# STlink.net
KiCad netlist of a schematic drawn in Altium Designer
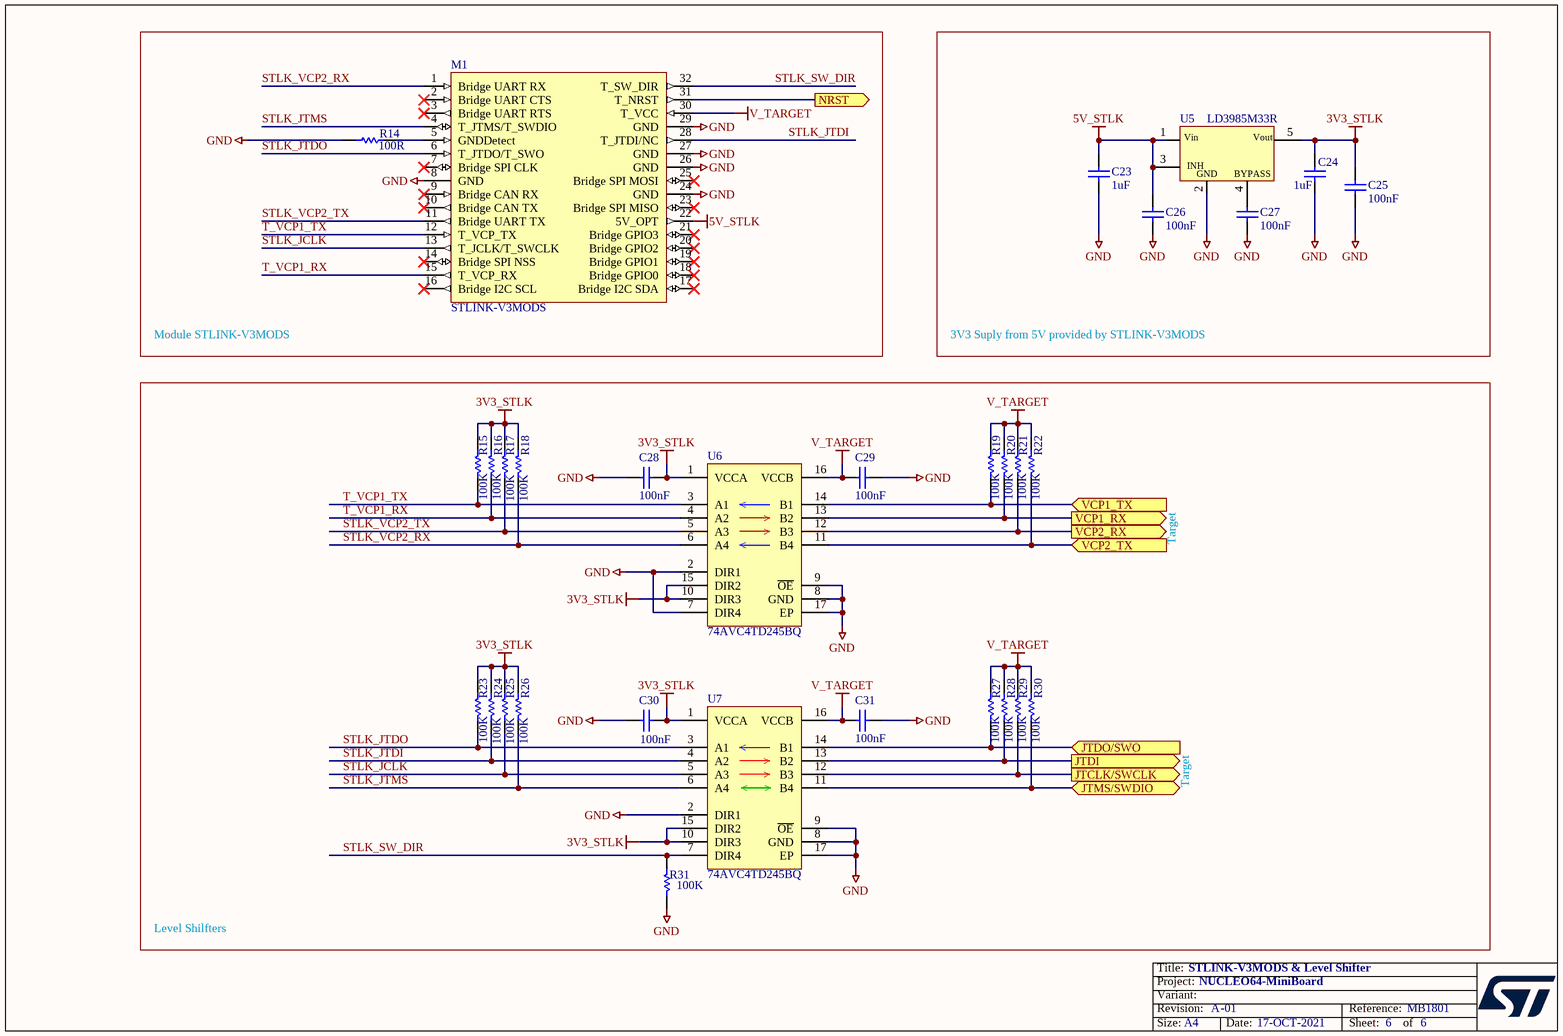
[diagram p0: STlink.SchDoc]

(export (version "E")
  (design (tool "Eeschema 10.0.6"))
  (components
    (comp (ref "C23")
      (value "1uF")
      (footprint "C0402")
      (description "Capacitor, MLCC, 1uF, 10V, X5R, +/-10%, 0402, T=0.5mm")
      (fields
        (field (name "INTERNAL_PART_NUMBER") "MCD-01722")
        (field (name "MANUFACTURER_PART_NUMBER") "CC0402KRX5R6BB105")
      )
      (libsource (lib "MCD_PARTS_database") (part "Capacitor"))
    )
    (comp (ref "C24")
      (value "1uF")
      (footprint "C0402")
      (description "Capacitor, MLCC, 1uF, 10V, X5R, +/-10%, 0402, T=0.5mm")
      (fields
        (field (name "INTERNAL_PART_NUMBER") "MCD-01722")
        (field (name "MANUFACTURER_PART_NUMBER") "CC0402KRX5R6BB105")
      )
      (libsource (lib "MCD_PARTS_database") (part "Capacitor"))
    )
    (comp (ref "C25")
      (value "100nF")
      (footprint "C0402")
      (description "Capacitor, MLCC, 100nF, 25V, X7R, +/-10%, 0402, T=0.5mm")
      (fields (field (name "INTERNAL_PART_NUMBER") "MCD-02355") (field (name "MANUFACTURER") "WALSIN"))
      (libsource (lib "MCD_PARTS_database") (part "Capacitor"))
    )
    (comp (ref "C26")
      (value "100nF")
      (footprint "C0402")
      (description "Capacitor, MLCC, 100nF, 25V, X7R, +/-10%, 0402, T=0.5mm")
      (fields (field (name "INTERNAL_PART_NUMBER") "MCD-02355") (field (name "MANUFACTURER") "WALSIN"))
      (libsource (lib "MCD_PARTS_database") (part "Capacitor"))
    )
    (comp (ref "C27")
      (value "100nF")
      (footprint "C0402")
      (description "Capacitor, MLCC, 100nF, 25V, X7R, +/-10%, 0402, T=0.5mm")
      (fields (field (name "INTERNAL_PART_NUMBER") "MCD-02355") (field (name "MANUFACTURER") "WALSIN"))
      (libsource (lib "MCD_PARTS_database") (part "Capacitor"))
    )
    (comp (ref "C28")
      (value "100nF")
      (footprint "C0402")
      (description "Capacitor, MLCC, 100nF, 25V, X7R, +/-10%, 0402, T=0.5mm")
      (fields (field (name "INTERNAL_PART_NUMBER") "MCD-02355") (field (name "MANUFACTURER") "WALSIN"))
      (libsource (lib "MCD_PARTS_database") (part "Capacitor"))
    )
    (comp (ref "C29")
      (value "100nF")
      (footprint "C0402")
      (description "Capacitor, MLCC, 100nF, 25V, X7R, +/-10%, 0402, T=0.5mm")
      (fields (field (name "INTERNAL_PART_NUMBER") "MCD-02355") (field (name "MANUFACTURER") "WALSIN"))
      (libsource (lib "MCD_PARTS_database") (part "Capacitor"))
    )
    (comp (ref "C30")
      (value "100nF")
      (footprint "C0402")
      (description "Capacitor, MLCC, 100nF, 25V, X7R, +/-10%, 0402, T=0.5mm")
      (fields (field (name "INTERNAL_PART_NUMBER") "MCD-02355") (field (name "MANUFACTURER") "WALSIN"))
      (libsource (lib "MCD_PARTS_database") (part "Capacitor"))
    )
    (comp (ref "C31")
      (value "100nF")
      (footprint "C0402")
      (description "Capacitor, MLCC, 100nF, 25V, X7R, +/-10%, 0402, T=0.5mm")
      (fields (field (name "INTERNAL_PART_NUMBER") "MCD-02355") (field (name "MANUFACTURER") "WALSIN"))
      (libsource (lib "MCD_PARTS_database") (part "Capacitor"))
    )
    (comp (ref "M1")
      (value "STLINK-V3MODS")
      (footprint "MOD_STLINK-V3M_MB1467")
      (description "STLINK-V3MODS module")
      (fields
        (field (name "INTERNAL_PART_NUMBER") "MCD-01983")
        (field (name "MANUFACTURER") "STMICROELECTRONICS")
      )
      (libsource (lib "MCD_PARTS_database") (part "STLINK-V3MODS"))
    )
    (comp (ref "R14")
      (value "100R")
      (footprint "R0402")
      (description "Resistor, 100R, 0402, +/-1%, 1/16W")
      (fields (field (name "INTERNAL_PART_NUMBER") "MCD-00119") (field (name "MANUFACTURER") "YAGEO"))
      (libsource (lib "MCD_PARTS_database") (part "Resistor"))
    )
    (comp (ref "R15")
      (value "100K")
      (footprint "R0402")
      (description "Resistor, 100K, 0402, +/-1%, 1/16W")
      (fields
        (field (name "INTERNAL_PART_NUMBER") "MCD-00059")
        (field (name "MANUFACTURER_PART_NUMBER") "RC0402FR-07100KL")
      )
      (libsource (lib "MCD_PARTS_database") (part "Resistor"))
    )
    (comp (ref "R16")
      (value "100K")
      (footprint "R0402")
      (description "Resistor, 100K, 0402, +/-1%, 1/16W")
      (fields
        (field (name "INTERNAL_PART_NUMBER") "MCD-00059")
        (field (name "MANUFACTURER_PART_NUMBER") "RC0402FR-07100KL")
      )
      (libsource (lib "MCD_PARTS_database") (part "Resistor"))
    )
    (comp (ref "R17")
      (value "100K")
      (footprint "R0402")
      (description "Resistor, 100K, 0402, +/-1%, 1/16W")
      (fields
        (field (name "INTERNAL_PART_NUMBER") "MCD-00059")
        (field (name "MANUFACTURER_PART_NUMBER") "RC0402FR-07100KL")
      )
      (libsource (lib "MCD_PARTS_database") (part "Resistor"))
    )
    (comp (ref "R18")
      (value "100K")
      (footprint "R0402")
      (description "Resistor, 100K, 0402, +/-1%, 1/16W")
      (fields
        (field (name "INTERNAL_PART_NUMBER") "MCD-00059")
        (field (name "MANUFACTURER_PART_NUMBER") "RC0402FR-07100KL")
      )
      (libsource (lib "MCD_PARTS_database") (part "Resistor"))
    )
    (comp (ref "R19")
      (value "100K")
      (footprint "R0402")
      (description "Resistor, 100K, 0402, +/-1%, 1/16W")
      (fields
        (field (name "INTERNAL_PART_NUMBER") "MCD-00059")
        (field (name "MANUFACTURER_PART_NUMBER") "RC0402FR-07100KL")
      )
      (libsource (lib "MCD_PARTS_database") (part "Resistor"))
    )
    (comp (ref "R20")
      (value "100K")
      (footprint "R0402")
      (description "Resistor, 100K, 0402, +/-1%, 1/16W")
      (fields
        (field (name "INTERNAL_PART_NUMBER") "MCD-00059")
        (field (name "MANUFACTURER_PART_NUMBER") "RC0402FR-07100KL")
      )
      (libsource (lib "MCD_PARTS_database") (part "Resistor"))
    )
    (comp (ref "R21")
      (value "100K")
      (footprint "R0402")
      (description "Resistor, 100K, 0402, +/-1%, 1/16W")
      (fields
        (field (name "INTERNAL_PART_NUMBER") "MCD-00059")
        (field (name "MANUFACTURER_PART_NUMBER") "RC0402FR-07100KL")
      )
      (libsource (lib "MCD_PARTS_database") (part "Resistor"))
    )
    (comp (ref "R22")
      (value "100K")
      (footprint "R0402")
      (description "Resistor, 100K, 0402, +/-1%, 1/16W")
      (fields
        (field (name "INTERNAL_PART_NUMBER") "MCD-00059")
        (field (name "MANUFACTURER_PART_NUMBER") "RC0402FR-07100KL")
      )
      (libsource (lib "MCD_PARTS_database") (part "Resistor"))
    )
    (comp (ref "R23")
      (value "100K")
      (footprint "R0402")
      (description "Resistor, 100K, 0402, +/-1%, 1/16W")
      (fields
        (field (name "INTERNAL_PART_NUMBER") "MCD-00059")
        (field (name "MANUFACTURER_PART_NUMBER") "RC0402FR-07100KL")
      )
      (libsource (lib "MCD_PARTS_database") (part "Resistor"))
    )
    (comp (ref "R24")
      (value "100K")
      (footprint "R0402")
      (description "Resistor, 100K, 0402, +/-1%, 1/16W")
      (fields
        (field (name "INTERNAL_PART_NUMBER") "MCD-00059")
        (field (name "MANUFACTURER_PART_NUMBER") "RC0402FR-07100KL")
      )
      (libsource (lib "MCD_PARTS_database") (part "Resistor"))
    )
    (comp (ref "R25")
      (value "100K")
      (footprint "R0402")
      (description "Resistor, 100K, 0402, +/-1%, 1/16W")
      (fields
        (field (name "INTERNAL_PART_NUMBER") "MCD-00059")
        (field (name "MANUFACTURER_PART_NUMBER") "RC0402FR-07100KL")
      )
      (libsource (lib "MCD_PARTS_database") (part "Resistor"))
    )
    (comp (ref "R26")
      (value "100K")
      (footprint "R0402")
      (description "Resistor, 100K, 0402, +/-1%, 1/16W")
      (fields
        (field (name "INTERNAL_PART_NUMBER") "MCD-00059")
        (field (name "MANUFACTURER_PART_NUMBER") "RC0402FR-07100KL")
      )
      (libsource (lib "MCD_PARTS_database") (part "Resistor"))
    )
    (comp (ref "R27")
      (value "100K")
      (footprint "R0402")
      (description "Resistor, 100K, 0402, +/-1%, 1/16W")
      (fields
        (field (name "INTERNAL_PART_NUMBER") "MCD-00059")
        (field (name "MANUFACTURER_PART_NUMBER") "RC0402FR-07100KL")
      )
      (libsource (lib "MCD_PARTS_database") (part "Resistor"))
    )
    (comp (ref "R28")
      (value "100K")
      (footprint "R0402")
      (description "Resistor, 100K, 0402, +/-1%, 1/16W")
      (fields
        (field (name "INTERNAL_PART_NUMBER") "MCD-00059")
        (field (name "MANUFACTURER_PART_NUMBER") "RC0402FR-07100KL")
      )
      (libsource (lib "MCD_PARTS_database") (part "Resistor"))
    )
    (comp (ref "R29")
      (value "100K")
      (footprint "R0402")
      (description "Resistor, 100K, 0402, +/-1%, 1/16W")
      (fields
        (field (name "INTERNAL_PART_NUMBER") "MCD-00059")
        (field (name "MANUFACTURER_PART_NUMBER") "RC0402FR-07100KL")
      )
      (libsource (lib "MCD_PARTS_database") (part "Resistor"))
    )
    (comp (ref "R30")
      (value "100K")
      (footprint "R0402")
      (description "Resistor, 100K, 0402, +/-1%, 1/16W")
      (fields
        (field (name "INTERNAL_PART_NUMBER") "MCD-00059")
        (field (name "MANUFACTURER_PART_NUMBER") "RC0402FR-07100KL")
      )
      (libsource (lib "MCD_PARTS_database") (part "Resistor"))
    )
    (comp (ref "R31")
      (value "100K")
      (footprint "R0402")
      (description "Resistor, 100K, 0402, +/-1%, 1/16W")
      (fields
        (field (name "INTERNAL_PART_NUMBER") "MCD-00059")
        (field (name "MANUFACTURER_PART_NUMBER") "RC0402FR-07100KL")
      )
      (libsource (lib "MCD_PARTS_database") (part "Resistor"))
    )
    (comp (ref "U5")
      (value "LD3985M33R")
      (footprint "REG_SOT23-5L")
      (description "Ultra low drop-low noise BiCMOS voltage, regulators low ESR capacitors compatible")
      (fields
        (field (name "INTERNAL_PART_NUMBER") "MCD-00086")
        (field (name "MANUFACTURER") "STMICROELECTRONICS")
      )
      (libsource (lib "MCD_PARTS_database") (part "LD3985M33R"))
    )
    (comp (ref "U6")
      (value "74AVC4TD245BQ")
      (footprint "ICC_DHVQFN16-EPAD_SOT763-1_2P5X3P5_H0P85_P050")
      (description "4-bit dual supply translating transceiver with configurable voltage translation; 3-state")
      (fields
        (field (name "INTERNAL_PART_NUMBER") "MCD-01945")
        (field (name "MANUFACTURER_PART_NUMBER") "74AVC4TD245BQ,115")
      )
      (libsource (lib "MCD_PARTS_database") (part "74AVC4TD245BQ"))
    )
    (comp (ref "U7")
      (value "74AVC4TD245BQ")
      (footprint "ICC_DHVQFN16-EPAD_SOT763-1_2P5X3P5_H0P85_P050")
      (description "4-bit dual supply translating transceiver with configurable voltage translation; 3-state")
      (fields
        (field (name "INTERNAL_PART_NUMBER") "MCD-01945")
        (field (name "MANUFACTURER_PART_NUMBER") "74AVC4TD245BQ,115")
      )
      (libsource (lib "MCD_PARTS_database") (part "74AVC4TD245BQ"))
    )
  )
  (nets
    (net (code "1") (name "/JTCLK{slash}SWCLK") (class "Default")
      (node (ref "R29") (pin "1") (pinfunction "1_1") (pintype "passive"))
      (node (ref "U7") (pin "12") (pinfunction "B3_12") (pintype "passive"))
    )
    (net (code "2") (name "/JTDI") (class "Default")
      (node (ref "R28") (pin "1") (pinfunction "1_1") (pintype "passive"))
      (node (ref "U7") (pin "13") (pinfunction "B2_13") (pintype "passive"))
    )
    (net (code "3") (name "/JTDO{slash}SWO") (class "Default")
      (node (ref "R27") (pin "1") (pinfunction "1_1") (pintype "passive"))
      (node (ref "U7") (pin "14") (pinfunction "B1_14") (pintype "passive"))
    )
    (net (code "4") (name "/JTMS{slash}SWDIO") (class "Default")
      (node (ref "R30") (pin "1") (pinfunction "1_1") (pintype "passive"))
      (node (ref "U7") (pin "11") (pinfunction "B4_11") (pintype "passive"))
    )
    (net (code "5") (name "/NRST") (class "Default")
      (node (ref "M1") (pin "31") (pinfunction "T_NRST_31") (pintype "output"))
    )
    (net (code "6") (name "/STLK_JCLK") (class "Default")
      (node (ref "M1") (pin "13") (pinfunction "T_JCLK/T_SWCLK_13") (pintype "output"))
      (node (ref "R25") (pin "1") (pinfunction "1_1") (pintype "passive"))
      (node (ref "U7") (pin "5") (pinfunction "A3_5") (pintype "passive"))
    )
    (net (code "7") (name "/STLK_JTDI") (class "Default")
      (node (ref "M1") (pin "28") (pinfunction "T_JTDI/NC_28") (pintype "output"))
      (node (ref "R24") (pin "1") (pinfunction "1_1") (pintype "passive"))
      (node (ref "U7") (pin "4") (pinfunction "A2_4") (pintype "passive"))
    )
    (net (code "8") (name "/STLK_JTDO") (class "Default")
      (node (ref "M1") (pin "6") (pinfunction "T_JTDO/T_SWO_6") (pintype "input"))
      (node (ref "R23") (pin "1") (pinfunction "1_1") (pintype "passive"))
      (node (ref "U7") (pin "3") (pinfunction "A1_3") (pintype "passive"))
    )
    (net (code "9") (name "/STLK_JTMS") (class "Default")
      (node (ref "M1") (pin "4") (pinfunction "T_JTMS/T_SWDIO_4") (pintype "bidirectional"))
      (node (ref "R26") (pin "1") (pinfunction "1_1") (pintype "passive"))
      (node (ref "U7") (pin "6") (pinfunction "A4_6") (pintype "passive"))
    )
    (net (code "10") (name "/STLK_SW_DIR") (class "Default")
      (node (ref "M1") (pin "32") (pinfunction "T_SW_DIR_32") (pintype "output"))
      (node (ref "R31") (pin "1") (pinfunction "1_1") (pintype "passive"))
      (node (ref "U7") (pin "7") (pinfunction "DIR4_7") (pintype "passive"))
    )
    (net (code "11") (name "/STLK_VCP2_RX") (class "Default")
      (node (ref "M1") (pin "1") (pinfunction "Bridge_UART_RX_1") (pintype "input"))
      (node (ref "R18") (pin "1") (pinfunction "1_1") (pintype "passive"))
      (node (ref "U6") (pin "6") (pinfunction "A4_6") (pintype "passive"))
    )
    (net (code "12") (name "/STLK_VCP2_TX") (class "Default")
      (node (ref "M1") (pin "11") (pinfunction "Bridge_UART_TX_11") (pintype "output"))
      (node (ref "R17") (pin "1") (pinfunction "1_1") (pintype "passive"))
      (node (ref "U6") (pin "5") (pinfunction "A3_5") (pintype "passive"))
    )
    (net (code "13") (name "/T_VCP1_RX") (class "Default")
      (node (ref "M1") (pin "15") (pinfunction "T_VCP_RX_15") (pintype "output"))
      (node (ref "R16") (pin "1") (pinfunction "1_1") (pintype "passive"))
      (node (ref "U6") (pin "4") (pinfunction "A2_4") (pintype "passive"))
    )
    (net (code "14") (name "/T_VCP1_TX") (class "Default")
      (node (ref "M1") (pin "12") (pinfunction "T_VCP_TX_12") (pintype "input"))
      (node (ref "R15") (pin "1") (pinfunction "1_1") (pintype "passive"))
      (node (ref "U6") (pin "3") (pinfunction "A1_3") (pintype "passive"))
    )
    (net (code "15") (name "/VCP1_RX") (class "Default")
      (node (ref "R20") (pin "1") (pinfunction "1_1") (pintype "passive"))
      (node (ref "U6") (pin "13") (pinfunction "B2_13") (pintype "passive"))
    )
    (net (code "16") (name "/VCP1_TX") (class "Default")
      (node (ref "R19") (pin "1") (pinfunction "1_1") (pintype "passive"))
      (node (ref "U6") (pin "14") (pinfunction "B1_14") (pintype "passive"))
    )
    (net (code "17") (name "/VCP2_RX") (class "Default")
      (node (ref "R21") (pin "1") (pinfunction "1_1") (pintype "passive"))
      (node (ref "U6") (pin "12") (pinfunction "B3_12") (pintype "passive"))
    )
    (net (code "18") (name "/VCP2_TX") (class "Default")
      (node (ref "R22") (pin "1") (pinfunction "1_1") (pintype "passive"))
      (node (ref "U6") (pin "11") (pinfunction "B4_11") (pintype "passive"))
    )
    (net (code "19") (name "3V3_STLK") (class "Default")
      (node (ref "C24") (pin "2") (pinfunction "2_2") (pintype "passive"))
      (node (ref "C25") (pin "2") (pinfunction "2_2") (pintype "passive"))
      (node (ref "C28") (pin "1") (pinfunction "1_1") (pintype "passive"))
      (node (ref "C30") (pin "1") (pinfunction "1_1") (pintype "passive"))
      (node (ref "R15") (pin "2") (pinfunction "2_2") (pintype "passive"))
      (node (ref "R16") (pin "2") (pinfunction "2_2") (pintype "passive"))
      (node (ref "R17") (pin "2") (pinfunction "2_2") (pintype "passive"))
      (node (ref "R18") (pin "2") (pinfunction "2_2") (pintype "passive"))
      (node (ref "R23") (pin "2") (pinfunction "2_2") (pintype "passive"))
      (node (ref "R24") (pin "2") (pinfunction "2_2") (pintype "passive"))
      (node (ref "R25") (pin "2") (pinfunction "2_2") (pintype "passive"))
      (node (ref "R26") (pin "2") (pinfunction "2_2") (pintype "passive"))
      (node (ref "U5") (pin "5") (pinfunction "Vout_5") (pintype "passive"))
      (node (ref "U6") (pin "1") (pinfunction "VCCA_1") (pintype "passive"))
      (node (ref "U6") (pin "10") (pinfunction "DIR3_10") (pintype "passive"))
      (node (ref "U6") (pin "15") (pinfunction "DIR2_15") (pintype "passive"))
      (node (ref "U7") (pin "1") (pinfunction "VCCA_1") (pintype "passive"))
      (node (ref "U7") (pin "10") (pinfunction "DIR3_10") (pintype "passive"))
      (node (ref "U7") (pin "15") (pinfunction "DIR2_15") (pintype "passive"))
    )
    (net (code "20") (name "5V_STLK") (class "Default")
      (node (ref "C23") (pin "2") (pinfunction "2_2") (pintype "passive"))
      (node (ref "C26") (pin "2") (pinfunction "2_2") (pintype "passive"))
      (node (ref "M1") (pin "22") (pinfunction "5V_OPT_22") (pintype "output"))
      (node (ref "U5") (pin "1") (pinfunction "Vin_1") (pintype "passive"))
      (node (ref "U5") (pin "3") (pinfunction "CE_3") (pintype "passive"))
    )
    (net (code "21") (name "GND") (class "Default")
      (node (ref "C23") (pin "1") (pinfunction "1_1") (pintype "passive"))
      (node (ref "C24") (pin "1") (pinfunction "1_1") (pintype "passive"))
      (node (ref "C25") (pin "1") (pinfunction "1_1") (pintype "passive"))
      (node (ref "C26") (pin "1") (pinfunction "1_1") (pintype "passive"))
      (node (ref "C27") (pin "1") (pinfunction "1_1") (pintype "passive"))
      (node (ref "C28") (pin "2") (pinfunction "2_2") (pintype "passive"))
      (node (ref "C29") (pin "1") (pinfunction "1_1") (pintype "passive"))
      (node (ref "C30") (pin "2") (pinfunction "2_2") (pintype "passive"))
      (node (ref "C31") (pin "1") (pinfunction "1_1") (pintype "passive"))
      (node (ref "M1") (pin "24") (pinfunction "GND_24") (pintype "power_in"))
      (node (ref "M1") (pin "26") (pinfunction "GND_26") (pintype "power_in"))
      (node (ref "M1") (pin "27") (pinfunction "GND_27") (pintype "power_in"))
      (node (ref "M1") (pin "29") (pinfunction "GND_29") (pintype "power_in"))
      (node (ref "M1") (pin "8") (pinfunction "GND_8") (pintype "power_in"))
      (node (ref "R14") (pin "1") (pinfunction "1_1") (pintype "passive"))
      (node (ref "R31") (pin "2") (pinfunction "2_2") (pintype "passive"))
      (node (ref "U5") (pin "2") (pinfunction "GND_2") (pintype "passive"))
      (node (ref "U6") (pin "17") (pinfunction "EP_17") (pintype "passive"))
      (node (ref "U6") (pin "2") (pinfunction "DIR1_2") (pintype "passive"))
      (node (ref "U6") (pin "7") (pinfunction "DIR4_7") (pintype "passive"))
      (node (ref "U6") (pin "8") (pinfunction "GND_8") (pintype "passive"))
      (node (ref "U6") (pin "9") (pinfunction "~{OE}_9") (pintype "passive"))
      (node (ref "U7") (pin "17") (pinfunction "EP_17") (pintype "passive"))
      (node (ref "U7") (pin "2") (pinfunction "DIR1_2") (pintype "passive"))
      (node (ref "U7") (pin "8") (pinfunction "GND_8") (pintype "passive"))
      (node (ref "U7") (pin "9") (pinfunction "~{OE}_9") (pintype "passive"))
    )
    (net (code "22") (name "Net-(M1-GNDDetect)") (class "Default")
      (node (ref "M1") (pin "5") (pinfunction "GNDDetect_5") (pintype "input"))
      (node (ref "R14") (pin "2") (pinfunction "2_2") (pintype "passive"))
    )
    (net (code "23") (name "Net-(U5-BYPASS)") (class "Default")
      (node (ref "C27") (pin "2") (pinfunction "2_2") (pintype "passive"))
      (node (ref "U5") (pin "4") (pinfunction "BYPASS_4") (pintype "passive"))
    )
    (net (code "24") (name "V_TARGET") (class "Default")
      (node (ref "C29") (pin "2") (pinfunction "2_2") (pintype "passive"))
      (node (ref "C31") (pin "2") (pinfunction "2_2") (pintype "passive"))
      (node (ref "M1") (pin "30") (pinfunction "T_VCC_30") (pintype "input"))
      (node (ref "R19") (pin "2") (pinfunction "2_2") (pintype "passive"))
      (node (ref "R20") (pin "2") (pinfunction "2_2") (pintype "passive"))
      (node (ref "R21") (pin "2") (pinfunction "2_2") (pintype "passive"))
      (node (ref "R22") (pin "2") (pinfunction "2_2") (pintype "passive"))
      (node (ref "R27") (pin "2") (pinfunction "2_2") (pintype "passive"))
      (node (ref "R28") (pin "2") (pinfunction "2_2") (pintype "passive"))
      (node (ref "R29") (pin "2") (pinfunction "2_2") (pintype "passive"))
      (node (ref "R30") (pin "2") (pinfunction "2_2") (pintype "passive"))
      (node (ref "U6") (pin "16") (pinfunction "VCCB_16") (pintype "passive"))
      (node (ref "U7") (pin "16") (pinfunction "VCCB_16") (pintype "passive"))
    )
    (net (code "25") (name "unconnected-(M1-Bridge_CAN_RX-Pad9)") (class "Default")
      (node (ref "M1") (pin "9") (pinfunction "Bridge_CAN_RX_9") (pintype "input+no_connect"))
    )
    (net (code "26") (name "unconnected-(M1-Bridge_CAN_TX-Pad10)") (class "Default")
      (node (ref "M1") (pin "10") (pinfunction "Bridge_CAN_TX_10") (pintype "output+no_connect"))
    )
    (net (code "27") (name "unconnected-(M1-Bridge_GPIO0-Pad18)") (class "Default")
      (node (ref "M1") (pin "18") (pinfunction "Bridge_GPIO0_18") (pintype "bidirectional+no_connect"))
    )
    (net (code "28") (name "unconnected-(M1-Bridge_GPIO1-Pad19)") (class "Default")
      (node (ref "M1") (pin "19") (pinfunction "Bridge_GPIO1_19") (pintype "bidirectional+no_connect"))
    )
    (net (code "29") (name "unconnected-(M1-Bridge_GPIO2-Pad20)") (class "Default")
      (node (ref "M1") (pin "20") (pinfunction "Bridge_GPIO2_20") (pintype "bidirectional+no_connect"))
    )
    (net (code "30") (name "unconnected-(M1-Bridge_GPIO3-Pad21)") (class "Default")
      (node (ref "M1") (pin "21") (pinfunction "Bridge_GPIO3_21") (pintype "bidirectional+no_connect"))
    )
    (net (code "31") (name "unconnected-(M1-Bridge_I2C_SCL-Pad16)") (class "Default")
      (node (ref "M1") (pin "16") (pinfunction "Bridge_I2C_SCL_16") (pintype "output+no_connect"))
    )
    (net (code "32") (name "unconnected-(M1-Bridge_I2C_SDA-Pad17)") (class "Default")
      (node (ref "M1") (pin "17") (pinfunction "Bridge_I2C_SDA_17") (pintype "bidirectional+no_connect"))
    )
    (net (code "33") (name "unconnected-(M1-Bridge_SPI_CLK-Pad7)") (class "Default")
      (node (ref "M1") (pin "7") (pinfunction "Bridge_SPI_CLK_7") (pintype "bidirectional+no_connect"))
    )
    (net (code "34") (name "unconnected-(M1-Bridge_SPI_MISO-Pad23)") (class "Default")
      (node (ref "M1") (pin "23") (pinfunction "Bridge_SPI_MISO_23") (pintype "bidirectional+no_connect"))
    )
    (net (code "35") (name "unconnected-(M1-Bridge_SPI_MOSI-Pad25)") (class "Default")
      (node (ref "M1") (pin "25") (pinfunction "Bridge_SPI_MOSI_25") (pintype "bidirectional+no_connect"))
    )
    (net (code "36") (name "unconnected-(M1-Bridge_SPI_NSS-Pad14)") (class "Default")
      (node (ref "M1") (pin "14") (pinfunction "Bridge_SPI_NSS_14") (pintype "bidirectional+no_connect"))
    )
    (net (code "37") (name "unconnected-(M1-Bridge_UART_CTS-Pad2)") (class "Default")
      (node (ref "M1") (pin "2") (pinfunction "Bridge_UART_CTS_2") (pintype "input+no_connect"))
    )
    (net (code "38") (name "unconnected-(M1-Bridge_UART_RTS-Pad3)") (class "Default")
      (node (ref "M1") (pin "3") (pinfunction "Bridge_UART_RTS_3") (pintype "output+no_connect"))
    )
  )
)
